# smoggie.net
KiCad netlist of a schematic drawn in EAGLE
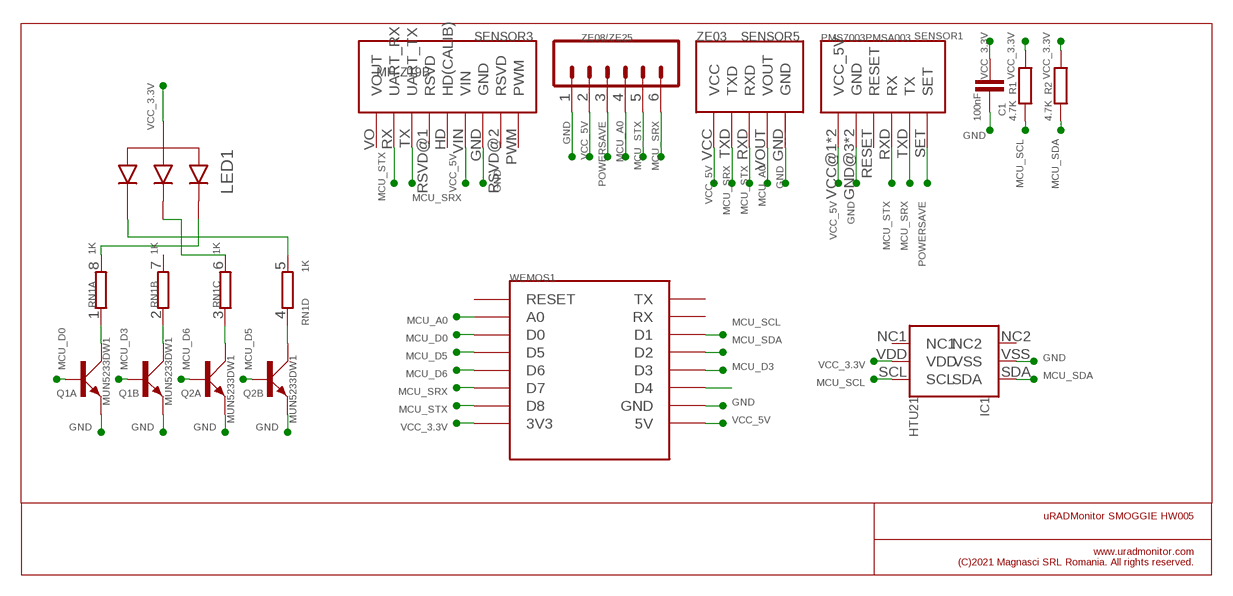
[diagram p0: schematic, sheet 1]

(export (version "E")
  (design (tool "Eeschema 10.0.6"))
  (components
    (comp (ref "C1")
      (value "100nF")
      (footprint "eagle-import:C0603")
      (libsource (lib "eagle-import") (part "C-EUC0603"))
    )
    (comp (ref "IC1")
      (value "HTU21")
      (footprint "eagle-import:SHT21")
      (libsource (lib "eagle-import") (part "SHT21SMDSMD"))
    )
    (comp (ref "LED1")
      (value "LED_1615_RGB_CA")
      (footprint "eagle-import:1615_LED_CA")
      (libsource (lib "eagle-import") (part "LED_1615_RGB_CA"))
    )
    (comp (ref "Q1")
      (value "MUN5233DW1")
      (footprint "eagle-import:SOT363_PHILIPS")
      (libsource (lib "eagle-import") (part "BC847BS"))
    )
    (comp (ref "Q2")
      (value "MUN5233DW1")
      (footprint "eagle-import:SOT363_PHILIPS")
      (libsource (lib "eagle-import") (part "BC847BS"))
    )
    (comp (ref "R1")
      (value "4.7K")
      (footprint "eagle-import:R0603")
      (libsource (lib "eagle-import") (part "R-EU_R0603"))
    )
    (comp (ref "R2")
      (value "4.7K")
      (footprint "eagle-import:R0603")
      (libsource (lib "eagle-import") (part "R-EU_R0603"))
    )
    (comp (ref "RN1")
      (value "1K")
      (footprint "eagle-import:0603-ARC")
      (libsource (lib "eagle-import") (part "4R-N0603-ARC"))
    )
    (comp (ref "SENSOR1")
      (value "PMS7003PMSA003")
      (footprint "eagle-import:PMSA003")
      (libsource (lib "eagle-import") (part "PMS7003PMSA003"))
    )
    (comp (ref "SENSOR3")
      (value "MH-Z19B")
      (footprint "eagle-import:MH-Z19B")
      (libsource (lib "eagle-import") (part "MH-Z19B"))
    )
    (comp (ref "SENSOR5")
      (value "ZE03")
      (footprint "eagle-import:ZE03")
      (libsource (lib "eagle-import") (part "ZE03"))
    )
    (comp (ref "WEMOS1")
      (value "11")
      (footprint "eagle-import:WEMOS-D1-MINI")
      (libsource (lib "eagle-import") (part "WEMOS-D1-MINI"))
    )
    (comp (ref "ZE08/ZE25")
      (value "M06SIP")
      (footprint "eagle-import:1X06")
      (libsource (lib "eagle-import") (part "M06SIP"))
    )
  )
  (nets
    (net (code "1") (name "/GND") (class "Default")
      (node (ref "C1") (pin "1") (pinfunction "1_1") (pintype "passive"))
      (node (ref "IC1") (pin "VSS") (pinfunction "VSS_VSS") (pintype "output"))
      (node (ref "Q1") (pin "1") (pinfunction "E_1") (pintype "passive"))
      (node (ref "Q1") (pin "4") (pinfunction "E_4") (pintype "passive"))
      (node (ref "Q2") (pin "1") (pinfunction "E_1") (pintype "passive"))
      (node (ref "Q2") (pin "4") (pinfunction "E_4") (pintype "passive"))
      (node (ref "SENSOR1") (pin "GND@3") (pinfunction "GND_GND@3") (pintype "bidirectional"))
      (node (ref "SENSOR1") (pin "GND@4") (pinfunction "GND_GND@4") (pintype "bidirectional"))
      (node (ref "SENSOR3") (pin "GND") (pinfunction "GND_GND") (pintype "bidirectional"))
      (node (ref "SENSOR5") (pin "GND") (pinfunction "GND_GND") (pintype "bidirectional"))
      (node (ref "WEMOS1") (pin "GND") (pinfunction "GND_GND") (pintype "bidirectional"))
      (node (ref "ZE08/ZE25") (pin "1") (pinfunction "1_1") (pintype "passive"))
    )
    (net (code "2") (name "/MCU_A0") (class "Default")
      (node (ref "SENSOR5") (pin "VOUT") (pinfunction "VOUT_VOUT") (pintype "bidirectional"))
      (node (ref "WEMOS1") (pin "A0") (pinfunction "A0_A0") (pintype "bidirectional"))
      (node (ref "ZE08/ZE25") (pin "4") (pinfunction "4_4") (pintype "passive"))
    )
    (net (code "3") (name "/MCU_D0") (class "Default")
      (node (ref "Q1") (pin "2") (pinfunction "B_2") (pintype "passive"))
      (node (ref "WEMOS1") (pin "D0") (pinfunction "D0_D0") (pintype "bidirectional"))
    )
    (net (code "4") (name "/MCU_D3") (class "Default")
      (node (ref "Q1") (pin "5") (pinfunction "B_5") (pintype "passive"))
      (node (ref "WEMOS1") (pin "D3") (pinfunction "D3_D3") (pintype "bidirectional"))
    )
    (net (code "5") (name "/MCU_D5") (class "Default")
      (node (ref "Q2") (pin "5") (pinfunction "B_5") (pintype "passive"))
      (node (ref "WEMOS1") (pin "D5") (pinfunction "D5_D5") (pintype "bidirectional"))
    )
    (net (code "6") (name "/MCU_D6") (class "Default")
      (node (ref "Q2") (pin "2") (pinfunction "B_2") (pintype "passive"))
      (node (ref "WEMOS1") (pin "D6") (pinfunction "D6_D6") (pintype "bidirectional"))
    )
    (net (code "7") (name "/MCU_SCL") (class "Default")
      (node (ref "IC1") (pin "SCL") (pinfunction "SCL_SCL") (pintype "power_in"))
      (node (ref "R1") (pin "2") (pinfunction "2_2") (pintype "passive"))
      (node (ref "WEMOS1") (pin "D1") (pinfunction "D1_D1") (pintype "bidirectional"))
    )
    (net (code "8") (name "/MCU_SDA") (class "Default")
      (node (ref "IC1") (pin "SDA") (pinfunction "SDA_SDA") (pintype "power_in"))
      (node (ref "R2") (pin "2") (pinfunction "2_2") (pintype "passive"))
      (node (ref "WEMOS1") (pin "D2") (pinfunction "D2_D2") (pintype "bidirectional"))
    )
    (net (code "9") (name "/MCU_SRX") (class "Default")
      (node (ref "SENSOR1") (pin "TXD") (pinfunction "TX_TXD") (pintype "bidirectional"))
      (node (ref "SENSOR3") (pin "TX") (pinfunction "UART_TX_TX") (pintype "bidirectional"))
      (node (ref "SENSOR5") (pin "TXD") (pinfunction "TXD_TXD") (pintype "bidirectional"))
      (node (ref "WEMOS1") (pin "D7") (pinfunction "D7_D7") (pintype "bidirectional"))
      (node (ref "ZE08/ZE25") (pin "6") (pinfunction "6_6") (pintype "passive"))
    )
    (net (code "10") (name "/MCU_STX") (class "Default")
      (node (ref "SENSOR1") (pin "RXD") (pinfunction "RX_RXD") (pintype "bidirectional"))
      (node (ref "SENSOR3") (pin "RX") (pinfunction "UART_RX_RX") (pintype "bidirectional"))
      (node (ref "SENSOR5") (pin "RXD") (pinfunction "RXD_RXD") (pintype "bidirectional"))
      (node (ref "WEMOS1") (pin "D8") (pinfunction "D8_D8") (pintype "bidirectional"))
      (node (ref "ZE08/ZE25") (pin "5") (pinfunction "5_5") (pintype "passive"))
    )
    (net (code "11") (name "/POWERSAVE") (class "Default")
      (node (ref "SENSOR1") (pin "SET") (pinfunction "SET_SET") (pintype "bidirectional"))
      (node (ref "ZE08/ZE25") (pin "3") (pinfunction "3_3") (pintype "passive"))
    )
    (net (code "12") (name "/VCC_3.3V") (class "Default")
      (node (ref "C1") (pin "2") (pinfunction "2_2") (pintype "passive"))
      (node (ref "IC1") (pin "VDD") (pinfunction "VDD_VDD") (pintype "input"))
      (node (ref "LED1") (pin "P$1") (pinfunction "P1_CA_P$1") (pintype "passive"))
      (node (ref "R1") (pin "1") (pinfunction "1_1") (pintype "passive"))
      (node (ref "R2") (pin "1") (pinfunction "1_1") (pintype "passive"))
      (node (ref "WEMOS1") (pin "3V3") (pinfunction "3V3_3V3") (pintype "bidirectional"))
    )
    (net (code "13") (name "/VCC_5V") (class "Default")
      (node (ref "SENSOR1") (pin "VCC@1") (pinfunction "VCC_5V_VCC@1") (pintype "bidirectional"))
      (node (ref "SENSOR1") (pin "VCC@2") (pinfunction "VCC_5V_VCC@2") (pintype "bidirectional"))
      (node (ref "SENSOR3") (pin "VIN") (pinfunction "VIN_VIN") (pintype "bidirectional"))
      (node (ref "SENSOR5") (pin "VCC") (pinfunction "VCC_VCC") (pintype "bidirectional"))
      (node (ref "WEMOS1") (pin "5V") (pinfunction "5V_5V") (pintype "bidirectional"))
      (node (ref "ZE08/ZE25") (pin "2") (pinfunction "2_2") (pintype "passive"))
    )
    (net (code "14") (name "Net-(LED1-P2_RED)") (class "Default")
      (node (ref "LED1") (pin "P$2") (pinfunction "P2_RED_P$2") (pintype "passive"))
      (node (ref "RN1") (pin "5") (pinfunction "2_5") (pintype "passive"))
    )
    (net (code "15") (name "Net-(LED1-P3_GREEN)") (class "Default")
      (node (ref "LED1") (pin "P$3") (pinfunction "P3_GREEN_P$3") (pintype "passive"))
      (node (ref "RN1") (pin "6") (pinfunction "2_6") (pintype "passive"))
    )
    (net (code "16") (name "Net-(LED1-P4_BLUE)") (class "Default")
      (node (ref "LED1") (pin "P$4") (pinfunction "P4_BLUE_P$4") (pintype "passive"))
      (node (ref "RN1") (pin "8") (pinfunction "2_8") (pintype "passive"))
    )
    (net (code "17") (name "Net-(Q1A-C)") (class "Default")
      (node (ref "Q1") (pin "6") (pinfunction "C_6") (pintype "passive"))
      (node (ref "RN1") (pin "1") (pinfunction "1_1") (pintype "passive"))
    )
    (net (code "18") (name "Net-(Q1B-C)") (class "Default")
      (node (ref "Q1") (pin "3") (pinfunction "C_3") (pintype "passive"))
      (node (ref "RN1") (pin "2") (pinfunction "1_2") (pintype "passive"))
    )
    (net (code "19") (name "Net-(Q2A-C)") (class "Default")
      (node (ref "Q2") (pin "6") (pinfunction "C_6") (pintype "passive"))
      (node (ref "RN1") (pin "3") (pinfunction "1_3") (pintype "passive"))
    )
    (net (code "20") (name "Net-(Q2B-C)") (class "Default")
      (node (ref "Q2") (pin "3") (pinfunction "C_3") (pintype "passive"))
      (node (ref "RN1") (pin "4") (pinfunction "1_4") (pintype "passive"))
    )
    (net (code "21") (name "unconnected-(IC1-PadNC1)") (class "Default")
      (node (ref "IC1") (pin "NC1") (pinfunction "NC1_NC1") (pintype "no_connect"))
    )
    (net (code "22") (name "unconnected-(IC1-PadNC2)") (class "Default")
      (node (ref "IC1") (pin "NC2") (pinfunction "NC2_NC2") (pintype "no_connect"))
    )
    (net (code "23") (name "unconnected-(RN1B-2-Pad7)") (class "Default")
      (node (ref "RN1") (pin "7") (pinfunction "2_7") (pintype "passive"))
    )
    (net (code "24") (name "unconnected-(SENSOR1-PadRESET)") (class "Default")
      (node (ref "SENSOR1") (pin "RESET") (pinfunction "RESET_RESET") (pintype "bidirectional"))
    )
    (net (code "25") (name "unconnected-(SENSOR3-HD(CALIB)-PadHD)") (class "Default")
      (node (ref "SENSOR3") (pin "HD") (pinfunction "HD(CALIB)_HD") (pintype "bidirectional"))
    )
    (net (code "26") (name "unconnected-(SENSOR3-PadPWM)") (class "Default")
      (node (ref "SENSOR3") (pin "PWM") (pinfunction "PWM_PWM") (pintype "bidirectional"))
    )
    (net (code "27") (name "unconnected-(SENSOR3-RSVD-PadRSVD@1)") (class "Default")
      (node (ref "SENSOR3") (pin "RSVD@1") (pinfunction "RSVD_RSVD@1") (pintype "bidirectional"))
    )
    (net (code "28") (name "unconnected-(SENSOR3-RSVD-PadRSVD@2)") (class "Default")
      (node (ref "SENSOR3") (pin "RSVD@2") (pinfunction "RSVD_RSVD@2") (pintype "bidirectional"))
    )
    (net (code "29") (name "unconnected-(SENSOR3-VOUT-PadVO)") (class "Default")
      (node (ref "SENSOR3") (pin "VO") (pinfunction "VOUT_VO") (pintype "bidirectional"))
    )
    (net (code "30") (name "unconnected-(WEMOS1-PadD4)") (class "Default")
      (node (ref "WEMOS1") (pin "D4") (pinfunction "D4_D4") (pintype "bidirectional"))
    )
    (net (code "31") (name "unconnected-(WEMOS1-PadRESET)") (class "Default")
      (node (ref "WEMOS1") (pin "RESET") (pinfunction "RESET_RESET") (pintype "bidirectional"))
    )
    (net (code "32") (name "unconnected-(WEMOS1-PadRX)") (class "Default")
      (node (ref "WEMOS1") (pin "RX") (pinfunction "RX_RX") (pintype "bidirectional"))
    )
    (net (code "33") (name "unconnected-(WEMOS1-PadTX)") (class "Default")
      (node (ref "WEMOS1") (pin "TX") (pinfunction "TX_TX") (pintype "bidirectional"))
    )
  )
)
